# Sheet1.net
KiCad netlist of a schematic drawn in Altium Designer
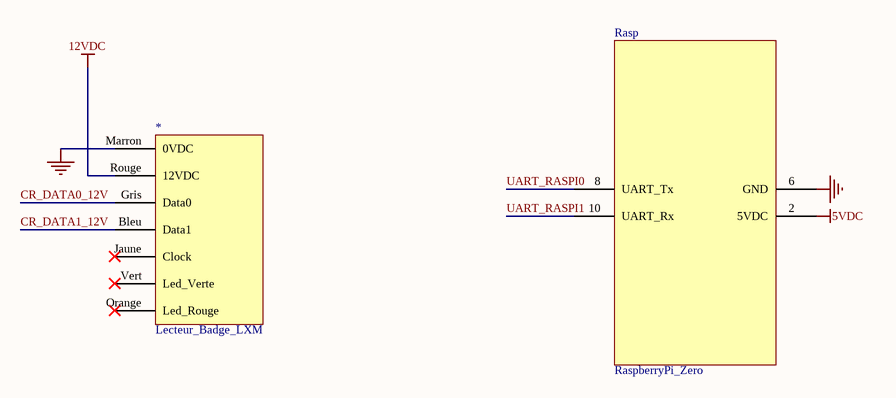
[diagram p0: Sheet1.SchDoc]

(export (version "E")
  (design (tool "Eeschema 10.0.6"))
  (components
    (comp (ref "*") (value "Lecteur_Badge_LXM") (libsource (lib "Schlib1") (part "Lecteur_Badge_LXM")))
    (comp (ref "Rasp") (value "RaspberryPi_Zero") (libsource (lib "Schlib1") (part "RaspberryPi_Zero")))
  )
  (nets
    (net (code "1") (name "/CR_DATA0_12V") (class "Default")
      (node (ref "*") (pin "Gris") (pinfunction "Data0_Gris") (pintype "passive"))
    )
    (net (code "2") (name "/CR_DATA1_12V") (class "Default")
      (node (ref "*") (pin "Bleu") (pinfunction "Data1_Bleu") (pintype "passive"))
    )
    (net (code "3") (name "/UART_RASPI0") (class "Default")
      (node (ref "Rasp") (pin "8") (pinfunction "UART_Tx_8") (pintype "passive"))
    )
    (net (code "4") (name "/UART_RASPI1") (class "Default")
      (node (ref "Rasp") (pin "10") (pinfunction "UART_Rx_10") (pintype "passive"))
    )
    (net (code "5") (name "5VDC") (class "Default")
      (node (ref "Rasp") (pin "2") (pinfunction "5VDC_2") (pintype "passive"))
    )
    (net (code "6") (name "12VDC") (class "Default")
      (node (ref "*") (pin "Rouge") (pinfunction "12VDC_Rouge") (pintype "passive"))
    )
    (net (code "7") (name "GND") (class "Default")
      (node (ref "*") (pin "Marron") (pinfunction "0VDC_Marron") (pintype "passive"))
      (node (ref "Rasp") (pin "6") (pinfunction "GND_6") (pintype "passive"))
    )
    (net (code "8") (name "unconnected-(*-Clock-PadJaune)") (class "Default")
      (node (ref "*") (pin "Jaune") (pinfunction "Clock_Jaune") (pintype "passive+no_connect"))
    )
    (net (code "9") (name "unconnected-(*-Led_Rouge-PadOrange)") (class "Default")
      (node (ref "*") (pin "Orange") (pinfunction "Led_Rouge_Orange") (pintype "passive+no_connect"))
    )
    (net (code "10") (name "unconnected-(*-Led_Verte-PadVert)") (class "Default")
      (node (ref "*") (pin "Vert") (pinfunction "Led_Verte_Vert") (pintype "passive+no_connect"))
    )
  )
)
